# Alight_main_board_v3.net
KiCad netlist of a schematic drawn in EAGLE
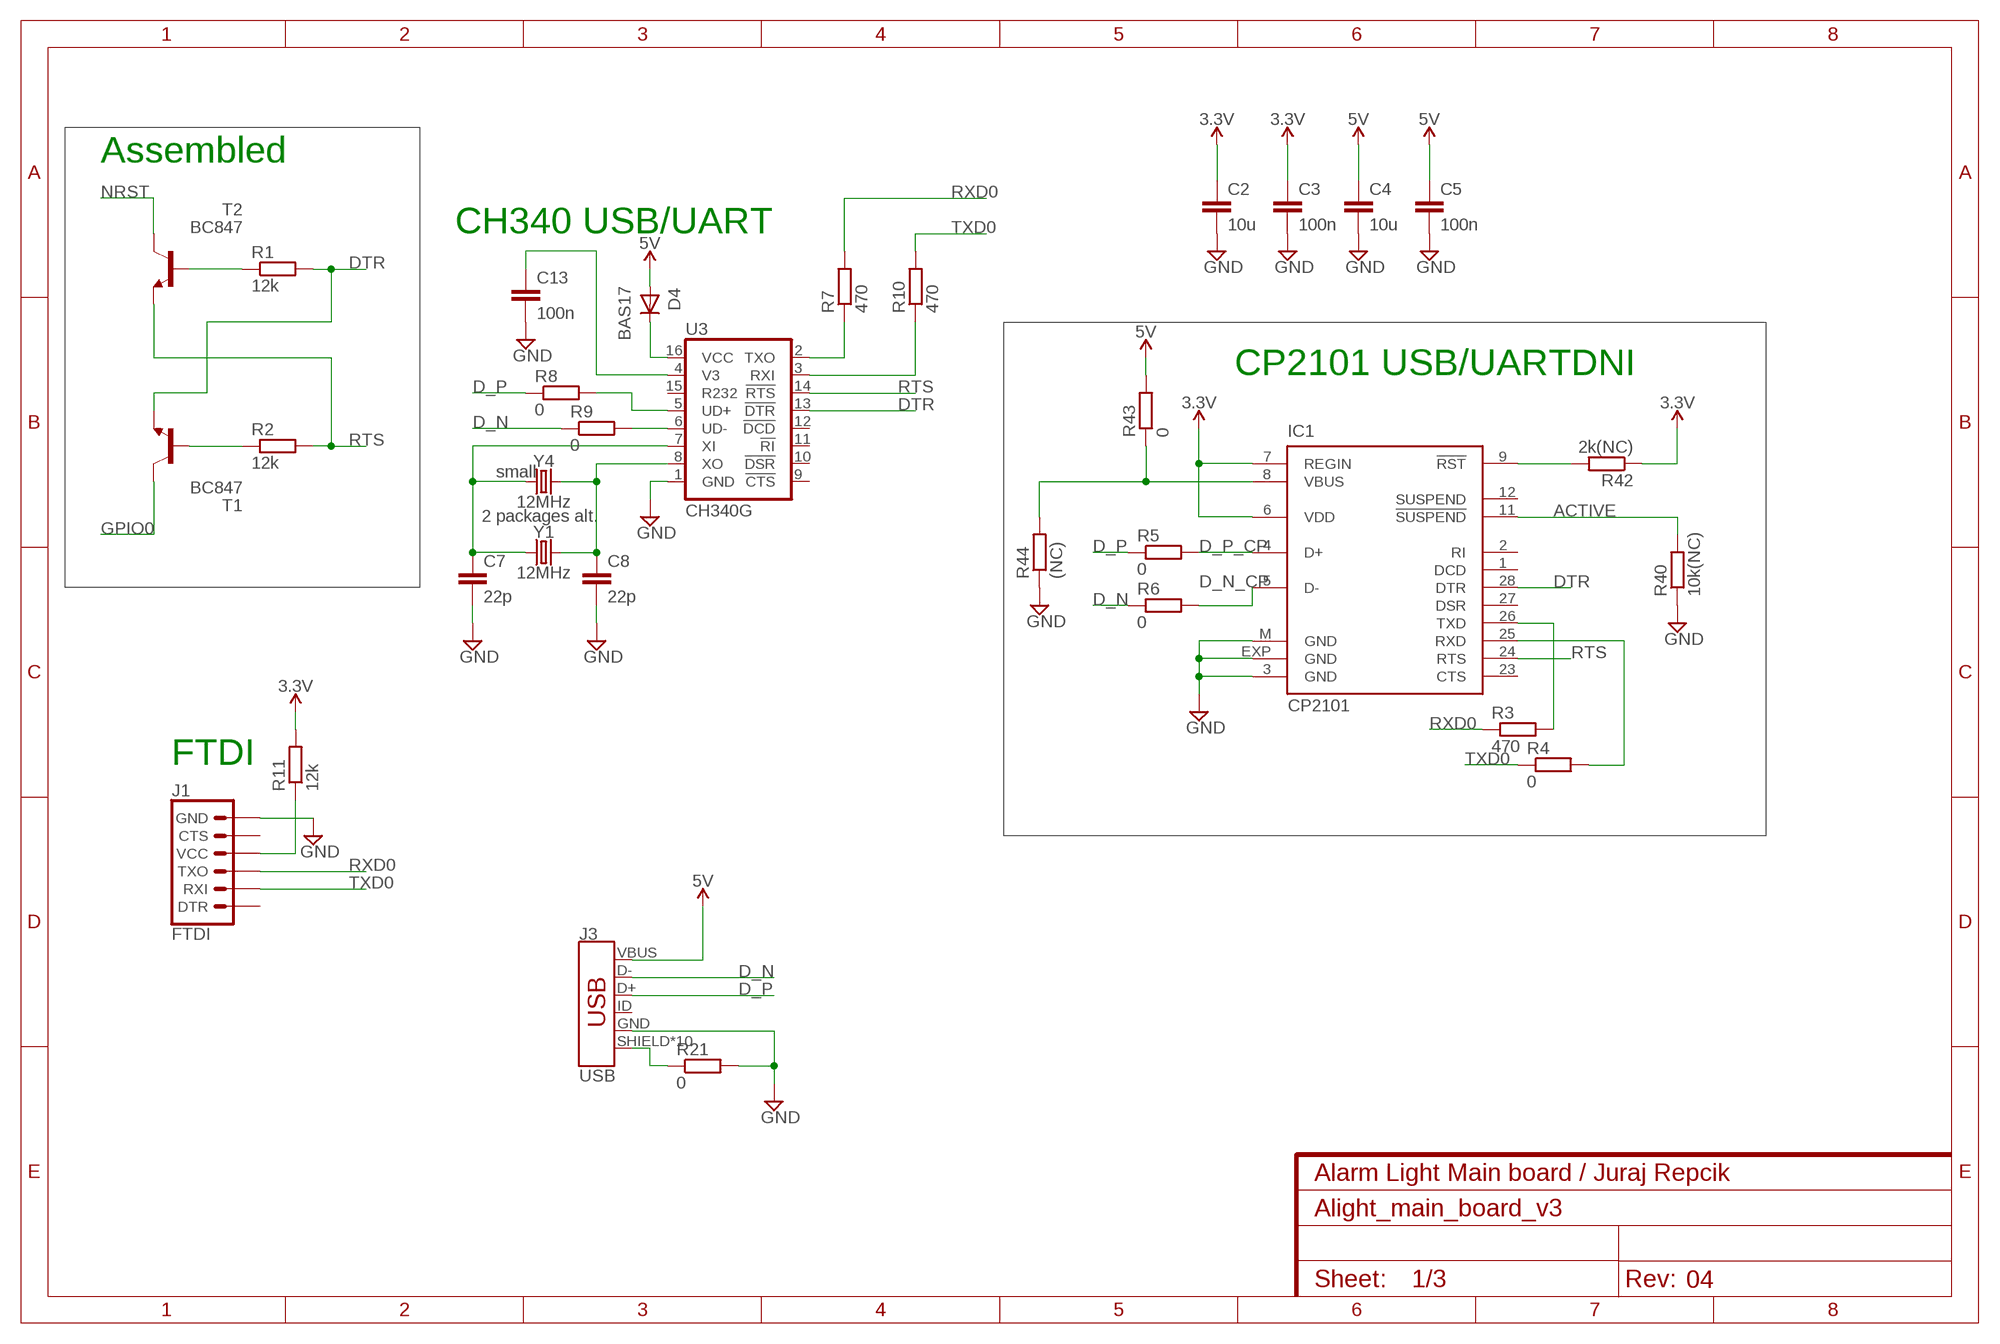
[diagram p0: schematic, sheet 1]
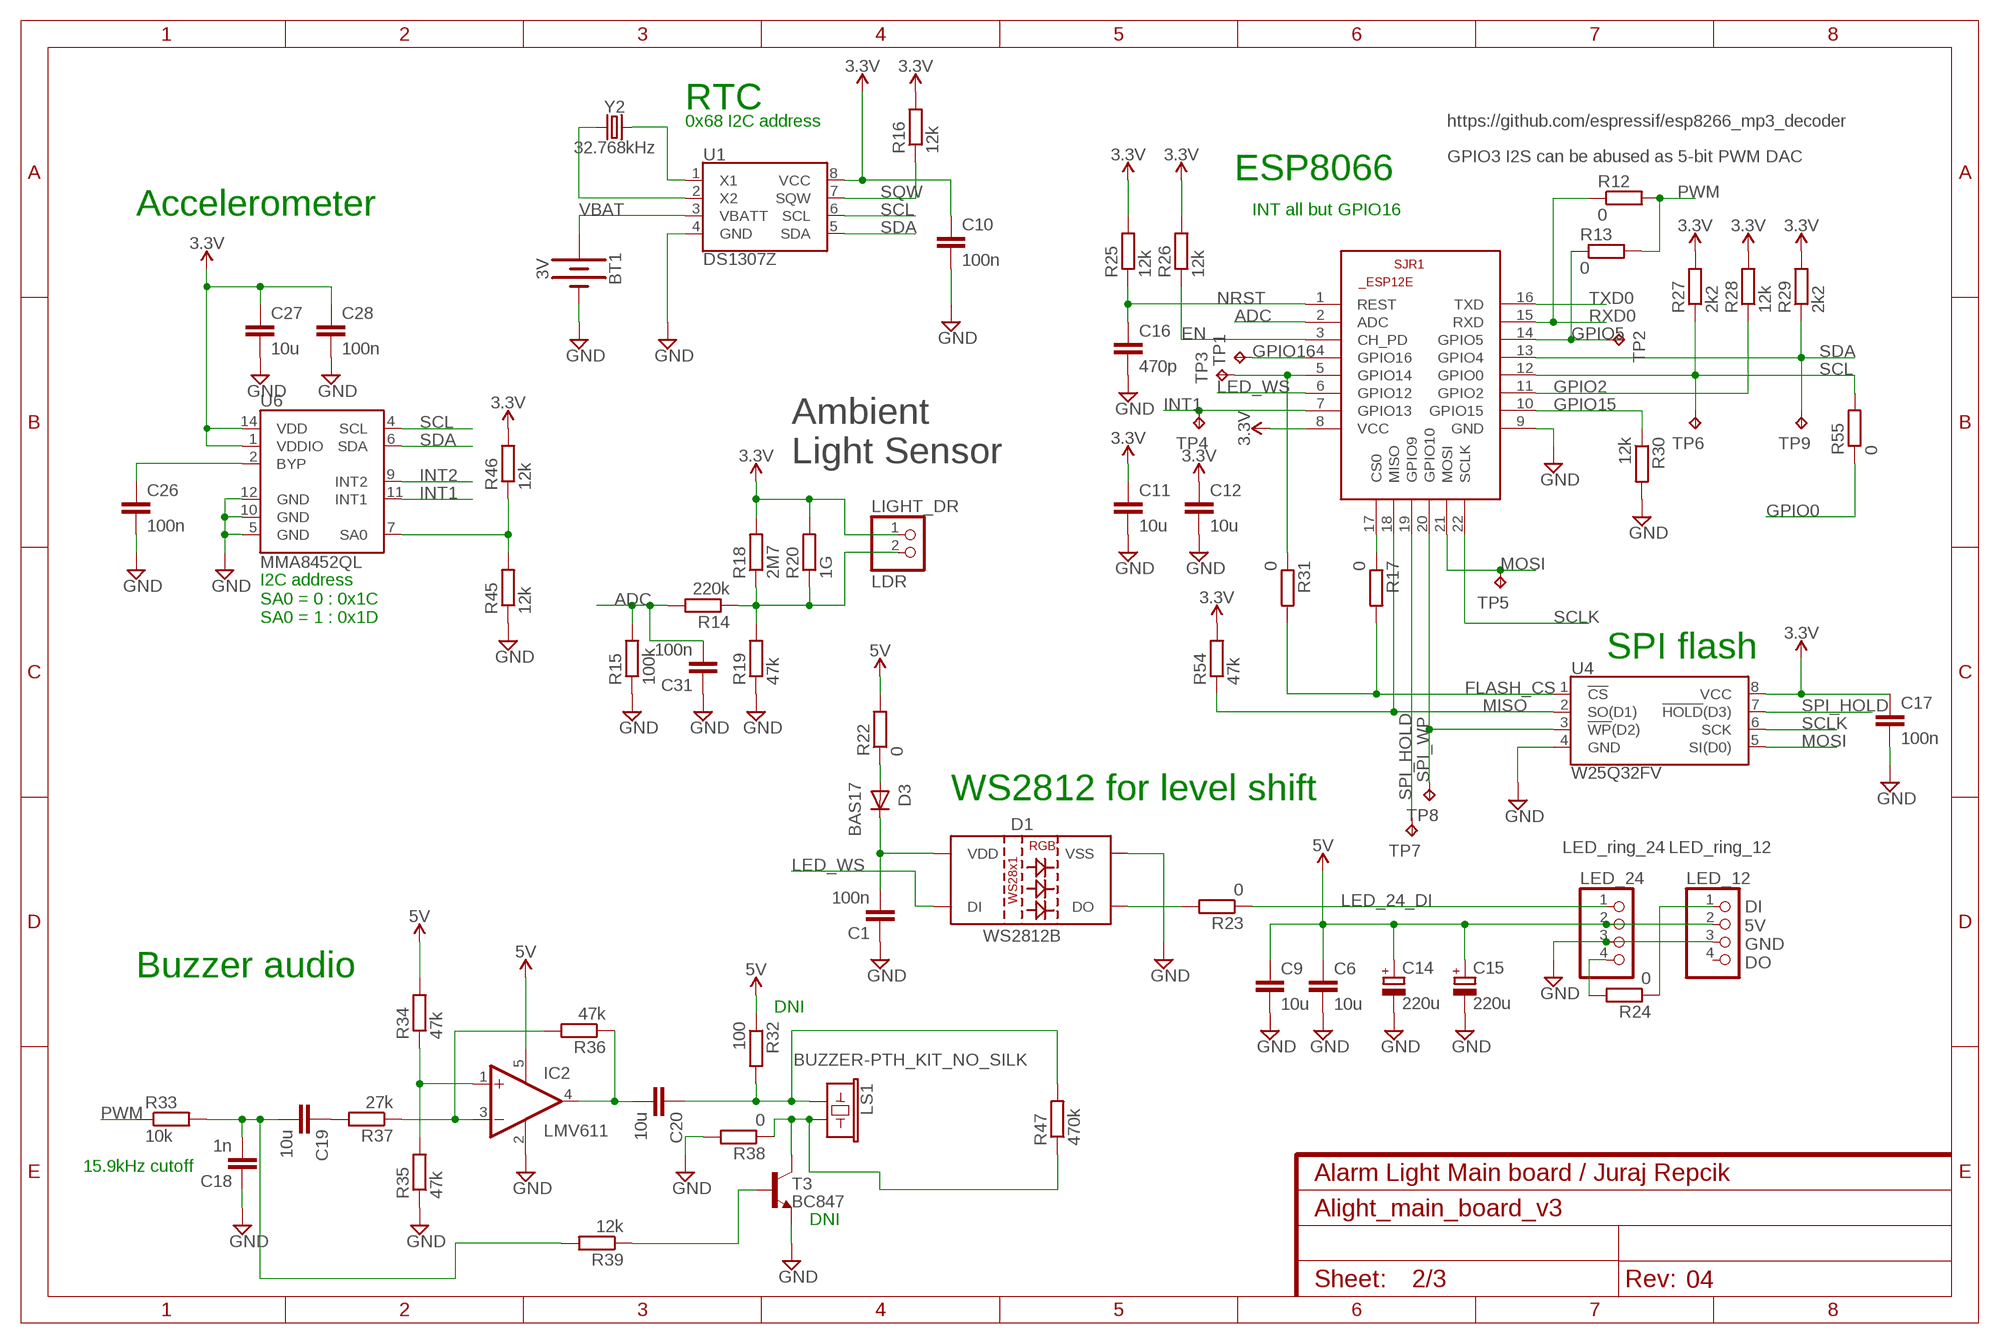
[diagram p1: schematic, sheet 2]
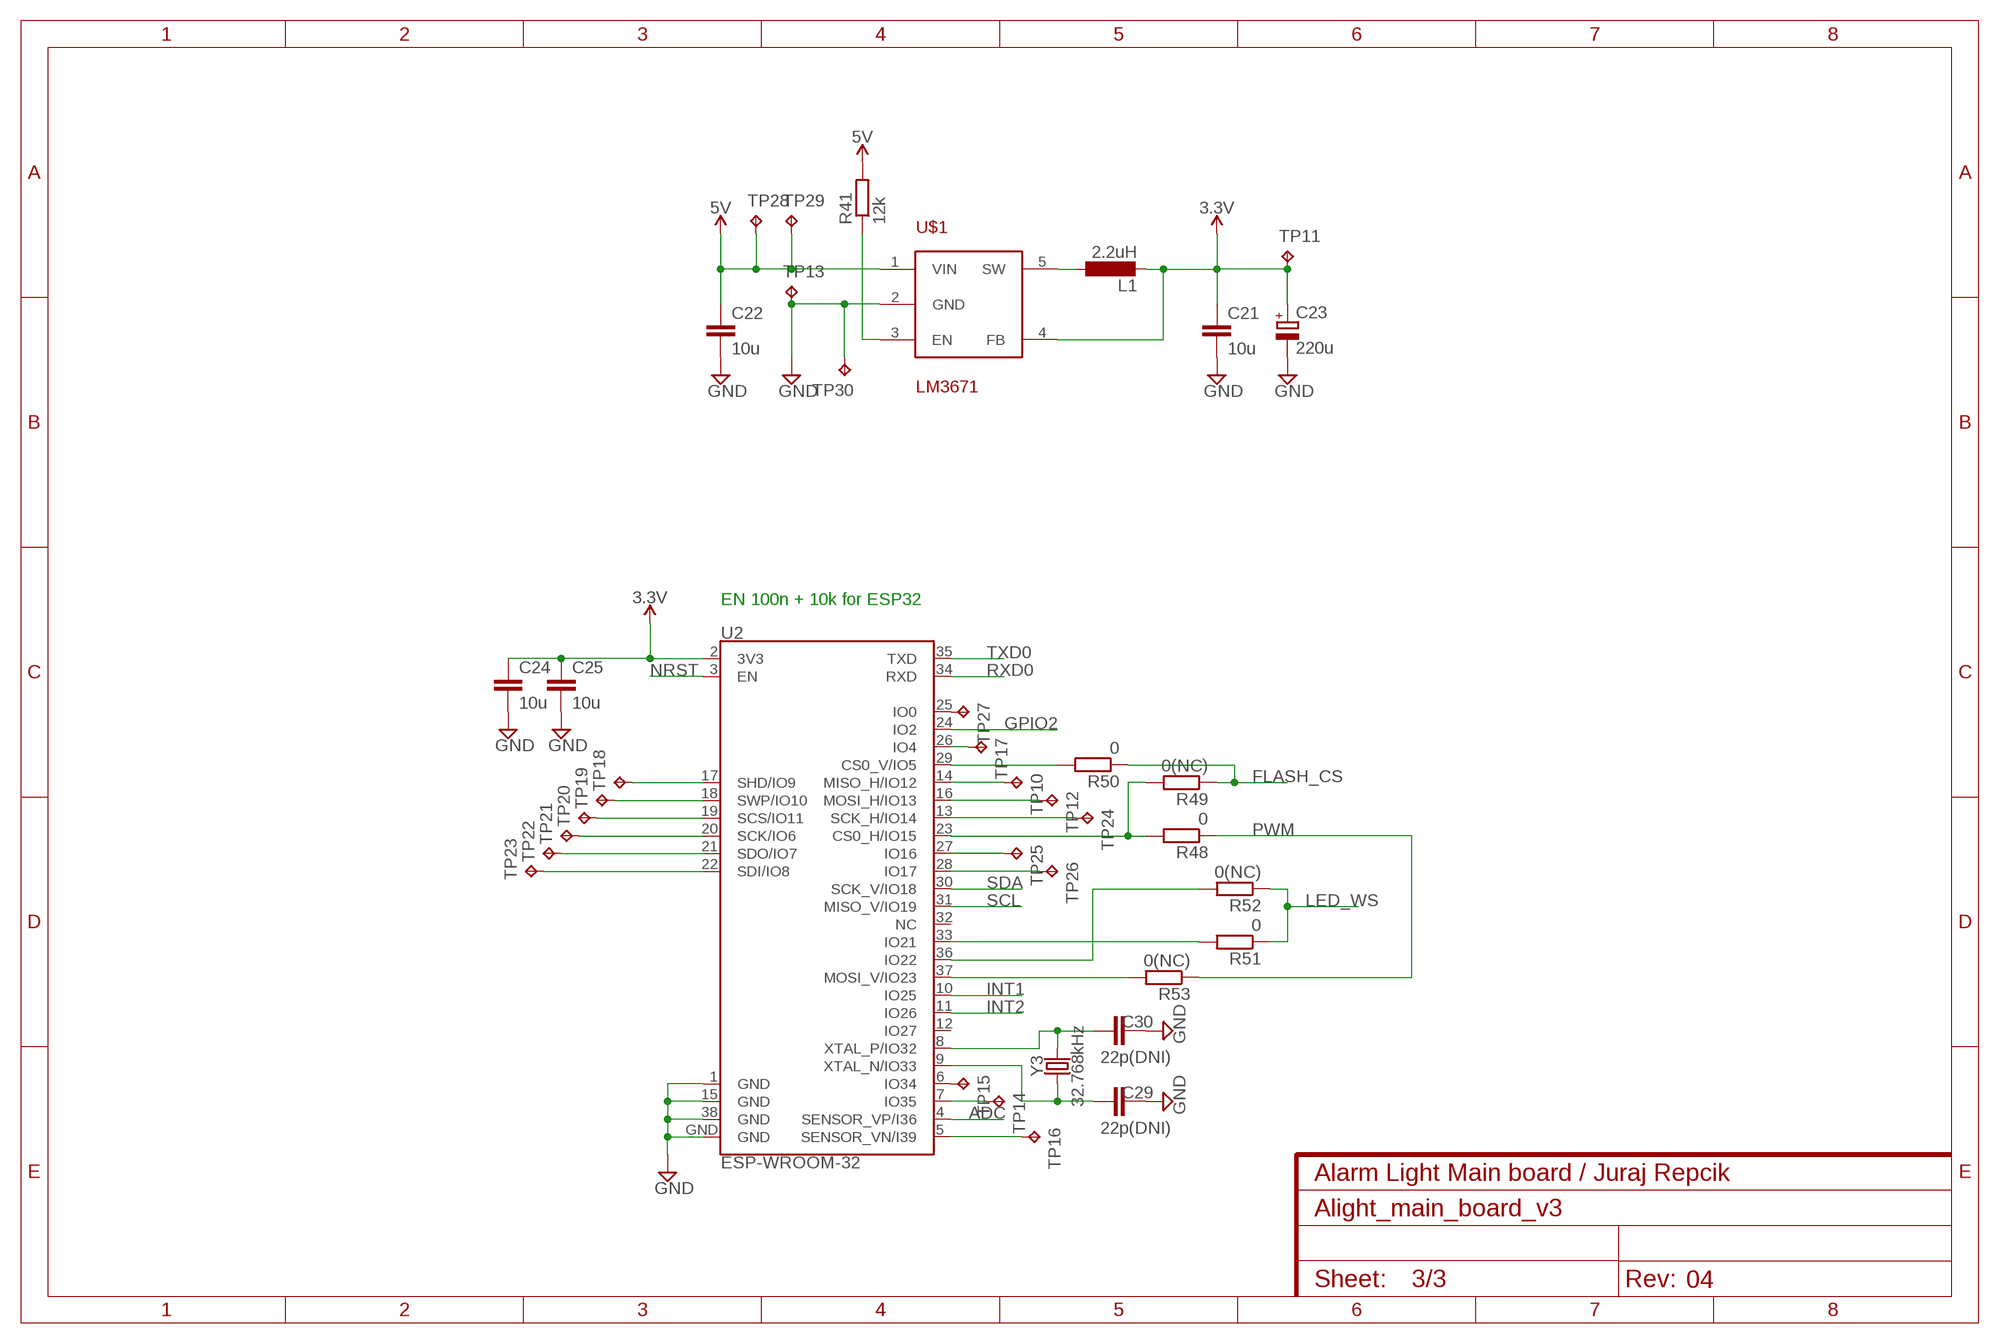
[diagram p2: schematic, sheet 3]

(export (version "E")
  (design (tool "Eeschema 10.0.6"))
  (components
    (comp (ref "C2")
      (value "10u")
      (footprint "eagle-import:C0603K")
      (libsource (lib "eagle-import") (part "C-EUC0603K"))
    )
    (comp (ref "C3")
      (value "100n")
      (footprint "eagle-import:C0603K")
      (libsource (lib "eagle-import") (part "C-EUC0603K"))
    )
    (comp (ref "C4")
      (value "10u")
      (footprint "eagle-import:C0603K")
      (libsource (lib "eagle-import") (part "C-EUC0603K"))
    )
    (comp (ref "C5")
      (value "100n")
      (footprint "eagle-import:C0603K")
      (libsource (lib "eagle-import") (part "C-EUC0603K"))
    )
    (comp (ref "C7")
      (value "22p")
      (footprint "eagle-import:C0402")
      (libsource (lib "eagle-import") (part "C-EUC0402"))
    )
    (comp (ref "C8")
      (value "22p")
      (footprint "eagle-import:C0402")
      (libsource (lib "eagle-import") (part "C-EUC0402"))
    )
    (comp (ref "C13")
      (value "100n")
      (footprint "eagle-import:C0603K")
      (libsource (lib "eagle-import") (part "C-EUC0603K"))
    )
    (comp (ref "D4")
      (value "BAS17")
      (footprint "eagle-import:SOT23")
      (libsource (lib "eagle-import") (part "BAS17"))
    )
    (comp (ref "IC1")
      (value "CP2101")
      (footprint "eagle-import:MLP28")
      (libsource (lib "eagle-import") (part "CP210X_USB_UART"))
    )
    (comp (ref "J1")
      (value "FTDI")
      (footprint "eagle-import:1X06_LONGPADS")
      (libsource (lib "eagle-import") (part "6_PIN_SERIAL_TARGETLONGPADS"))
    )
    (comp (ref "J3")
      (value "USB")
      (footprint "eagle-import:USB-MICROB-PTH-MILL")
      (libsource (lib "eagle-import") (part "USB_MICRO-B_HALF_PTH_MILL"))
    )
    (comp (ref "R1")
      (value "12k")
      (footprint "eagle-import:R0603")
      (libsource (lib "eagle-import") (part "R-EU_R0603"))
    )
    (comp (ref "R2")
      (value "12k")
      (footprint "eagle-import:R0603")
      (libsource (lib "eagle-import") (part "R-EU_R0603"))
    )
    (comp (ref "R3")
      (value "470")
      (footprint "eagle-import:R0603")
      (libsource (lib "eagle-import") (part "R-EU_R0603"))
    )
    (comp (ref "R4")
      (value "0")
      (footprint "eagle-import:R0603")
      (libsource (lib "eagle-import") (part "R-EU_R0603"))
    )
    (comp (ref "R5")
      (value "0")
      (footprint "eagle-import:R0603")
      (libsource (lib "eagle-import") (part "R-EU_R0603"))
    )
    (comp (ref "R6")
      (value "0")
      (footprint "eagle-import:R0603")
      (libsource (lib "eagle-import") (part "R-EU_R0603"))
    )
    (comp (ref "R7")
      (value "470")
      (footprint "eagle-import:R0603")
      (libsource (lib "eagle-import") (part "R-EU_R0603"))
    )
    (comp (ref "R8")
      (value "0")
      (footprint "eagle-import:R0603")
      (libsource (lib "eagle-import") (part "R-EU_R0603"))
    )
    (comp (ref "R9")
      (value "0")
      (footprint "eagle-import:R0603")
      (libsource (lib "eagle-import") (part "R-EU_R0603"))
    )
    (comp (ref "R10")
      (value "470")
      (footprint "eagle-import:R0603")
      (libsource (lib "eagle-import") (part "R-EU_R0603"))
    )
    (comp (ref "R11")
      (value "12k")
      (footprint "eagle-import:R0603")
      (libsource (lib "eagle-import") (part "R-EU_R0603"))
    )
    (comp (ref "R21")
      (value "0")
      (footprint "eagle-import:R0603")
      (libsource (lib "eagle-import") (part "R-EU_R0603"))
    )
    (comp (ref "R40")
      (value "10k(NC)")
      (footprint "eagle-import:R0603")
      (libsource (lib "eagle-import") (part "R-EU_R0603"))
    )
    (comp (ref "R42")
      (value "2k(NC)")
      (footprint "eagle-import:R0603")
      (libsource (lib "eagle-import") (part "R-EU_R0603"))
    )
    (comp (ref "R43")
      (value "0")
      (footprint "eagle-import:R0603")
      (libsource (lib "eagle-import") (part "R-EU_R0603"))
    )
    (comp (ref "R44")
      (value "(NC)")
      (footprint "eagle-import:R0603")
      (libsource (lib "eagle-import") (part "R-EU_R0603"))
    )
    (comp (ref "T1")
      (value "BC847")
      (footprint "eagle-import:SOT23")
      (libsource (lib "eagle-import") (part "transistor-neu-to92_BC847"))
    )
    (comp (ref "T2")
      (value "BC847")
      (footprint "eagle-import:SOT23")
      (libsource (lib "eagle-import") (part "transistor-neu-to92_BC847"))
    )
    (comp (ref "U3")
      (value "CH340G")
      (footprint "eagle-import:SO016")
      (libsource (lib "eagle-import") (part "CH340GSMD"))
    )
    (comp (ref "Y1")
      (value "12MHz")
      (footprint "eagle-import:HC49UP")
      (libsource (lib "eagle-import") (part "CRYSTALSMD-HC49UP"))
    )
    (comp (ref "Y4")
      (value "12MHz")
      (footprint "eagle-import:CRYSTAL-SMD-3.2X1.5MM")
      (libsource (lib "eagle-import") (part "CRYSTAL-32.768KHZSMD-3.2X1.5"))
    )
    (comp (ref "C21")
      (value "10u")
      (footprint "eagle-import:C0603K")
      (libsource (lib "eagle-import") (part "C-EUC0603K"))
    )
    (comp (ref "C22")
      (value "10u")
      (footprint "eagle-import:C0603K")
      (libsource (lib "eagle-import") (part "C-EUC0603K"))
    )
    (comp (ref "C23")
      (value "220u")
      (footprint "eagle-import:153CLV-0605")
      (libsource (lib "eagle-import") (part "CPOL-EU153CLV-0605"))
    )
    (comp (ref "C24")
      (value "10u")
      (footprint "eagle-import:C0603K")
      (libsource (lib "eagle-import") (part "C-EUC0603K"))
    )
    (comp (ref "C25")
      (value "10u")
      (footprint "eagle-import:C0603K")
      (libsource (lib "eagle-import") (part "C-EUC0603K"))
    )
    (comp (ref "C29")
      (value "22p(DNI)")
      (footprint "eagle-import:C0402")
      (libsource (lib "eagle-import") (part "C-EUC0402"))
    )
    (comp (ref "C30")
      (value "22p(DNI)")
      (footprint "eagle-import:C0402")
      (libsource (lib "eagle-import") (part "C-EUC0402"))
    )
    (comp (ref "L1")
      (value "2.2uH")
      (footprint "eagle-import:L3225M")
      (libsource (lib "eagle-import") (part "L-EUL3225M"))
    )
    (comp (ref "R41")
      (value "12k")
      (footprint "eagle-import:R0603")
      (libsource (lib "eagle-import") (part "R-EU_R0603"))
    )
    (comp (ref "R48")
      (value "0")
      (footprint "eagle-import:R0603")
      (libsource (lib "eagle-import") (part "R-EU_R0603"))
    )
    (comp (ref "R49")
      (value "0(NC)")
      (footprint "eagle-import:R0603")
      (libsource (lib "eagle-import") (part "R-EU_R0603"))
    )
    (comp (ref "R50")
      (value "0")
      (footprint "eagle-import:R0603")
      (libsource (lib "eagle-import") (part "R-EU_R0603"))
    )
    (comp (ref "R51")
      (value "0")
      (footprint "eagle-import:R0603")
      (libsource (lib "eagle-import") (part "R-EU_R0603"))
    )
    (comp (ref "R52")
      (value "0(NC)")
      (footprint "eagle-import:R0603")
      (libsource (lib "eagle-import") (part "R-EU_R0603"))
    )
    (comp (ref "R53")
      (value "0(NC)")
      (footprint "eagle-import:R0603")
      (libsource (lib "eagle-import") (part "R-EU_R0603"))
    )
    (comp (ref "TP10")
      (value "TPTP10R")
      (footprint "eagle-import:TP10R")
      (libsource (lib "eagle-import") (part "TPTP10R"))
    )
    (comp (ref "TP11")
      (value "TPTP10R")
      (footprint "eagle-import:TP10R")
      (libsource (lib "eagle-import") (part "TPTP10R"))
    )
    (comp (ref "TP12")
      (value "TPTP10R")
      (footprint "eagle-import:TP10R")
      (libsource (lib "eagle-import") (part "TPTP10R"))
    )
    (comp (ref "TP13")
      (value "TPTP10R")
      (footprint "eagle-import:TP10R")
      (libsource (lib "eagle-import") (part "TPTP10R"))
    )
    (comp (ref "TP14")
      (value "TPTP10R")
      (footprint "eagle-import:TP10R")
      (libsource (lib "eagle-import") (part "TPTP10R"))
    )
    (comp (ref "TP15")
      (value "TPTP10R")
      (footprint "eagle-import:TP10R")
      (libsource (lib "eagle-import") (part "TPTP10R"))
    )
    (comp (ref "TP16")
      (value "TPTP10R")
      (footprint "eagle-import:TP10R")
      (libsource (lib "eagle-import") (part "TPTP10R"))
    )
    (comp (ref "TP17")
      (value "TPTP10R")
      (footprint "eagle-import:TP10R")
      (libsource (lib "eagle-import") (part "TPTP10R"))
    )
    (comp (ref "TP18")
      (value "TPTP10R")
      (footprint "eagle-import:TP10R")
      (libsource (lib "eagle-import") (part "TPTP10R"))
    )
    (comp (ref "TP19")
      (value "TPTP10R")
      (footprint "eagle-import:TP10R")
      (libsource (lib "eagle-import") (part "TPTP10R"))
    )
    (comp (ref "TP20")
      (value "TPTP10R")
      (footprint "eagle-import:TP10R")
      (libsource (lib "eagle-import") (part "TPTP10R"))
    )
    (comp (ref "TP21")
      (value "TPTP10R")
      (footprint "eagle-import:TP10R")
      (libsource (lib "eagle-import") (part "TPTP10R"))
    )
    (comp (ref "TP22")
      (value "TPTP10R")
      (footprint "eagle-import:TP10R")
      (libsource (lib "eagle-import") (part "TPTP10R"))
    )
    (comp (ref "TP23")
      (value "TPTP10R")
      (footprint "eagle-import:TP10R")
      (libsource (lib "eagle-import") (part "TPTP10R"))
    )
    (comp (ref "TP24")
      (value "TPTP10R")
      (footprint "eagle-import:TP10R")
      (libsource (lib "eagle-import") (part "TPTP10R"))
    )
    (comp (ref "TP25")
      (value "TPTP10R")
      (footprint "eagle-import:TP10R")
      (libsource (lib "eagle-import") (part "TPTP10R"))
    )
    (comp (ref "TP26")
      (value "TPTP10R")
      (footprint "eagle-import:TP10R")
      (libsource (lib "eagle-import") (part "TPTP10R"))
    )
    (comp (ref "TP27")
      (value "TPTP10R")
      (footprint "eagle-import:TP10R")
      (libsource (lib "eagle-import") (part "TPTP10R"))
    )
    (comp (ref "TP28")
      (value "TPTP10R")
      (footprint "eagle-import:TP10R")
      (libsource (lib "eagle-import") (part "TPTP10R"))
    )
    (comp (ref "TP29")
      (value "TPTP10R")
      (footprint "eagle-import:TP10R")
      (libsource (lib "eagle-import") (part "TPTP10R"))
    )
    (comp (ref "TP30")
      (value "TPTP10R")
      (footprint "eagle-import:TP10R")
      (libsource (lib "eagle-import") (part "TPTP10R"))
    )
    (comp (ref "U$1")
      (value "LM3671")
      (footprint "eagle-import:SOT23-5")
      (libsource (lib "eagle-import") (part "LM3671"))
    )
    (comp (ref "U2")
      (value "ESP-WROOM-32")
      (footprint "eagle-import:ESP-WROOM-32")
      (libsource (lib "eagle-import") (part "ESP-WROOM-32"))
    )
    (comp (ref "Y3")
      (value "32.768kHz")
      (footprint "eagle-import:CRYSTAL-SMD-3.2X1.5MM")
      (libsource (lib "eagle-import") (part "CRYSTAL-32.768KHZSMD-3.2X1.5"))
    )
    (comp (ref "BT1")
      (value "3V")
      (footprint "eagle-import:BATTCOM_20MM_PTH_KIT")
      (libsource (lib "eagle-import") (part "BATTERY-20MM_PTH_KIT"))
    )
    (comp (ref "C1")
      (value "100n")
      (footprint "eagle-import:C0603K")
      (libsource (lib "eagle-import") (part "C-EUC0603K"))
    )
    (comp (ref "C6")
      (value "10u")
      (footprint "eagle-import:C0603K")
      (libsource (lib "eagle-import") (part "C-EUC0603K"))
    )
    (comp (ref "C9")
      (value "10u")
      (footprint "eagle-import:C0603K")
      (libsource (lib "eagle-import") (part "C-EUC0603K"))
    )
    (comp (ref "C10")
      (value "100n")
      (footprint "eagle-import:C0603K")
      (libsource (lib "eagle-import") (part "C-EUC0603K"))
    )
    (comp (ref "C11")
      (value "10u")
      (footprint "eagle-import:C0603K")
      (libsource (lib "eagle-import") (part "C-EUC0603K"))
    )
    (comp (ref "C12")
      (value "10u")
      (footprint "eagle-import:C0603K")
      (libsource (lib "eagle-import") (part "C-EUC0603K"))
    )
    (comp (ref "C14")
      (value "220u")
      (footprint "eagle-import:153CLV-0605")
      (libsource (lib "eagle-import") (part "CPOL-EU153CLV-0605"))
    )
    (comp (ref "C15")
      (value "220u")
      (footprint "eagle-import:153CLV-0605")
      (libsource (lib "eagle-import") (part "CPOL-EU153CLV-0605"))
    )
    (comp (ref "C16")
      (value "470p")
      (footprint "eagle-import:C0603K")
      (libsource (lib "eagle-import") (part "C-EUC0603K"))
    )
    (comp (ref "C17")
      (value "100n")
      (footprint "eagle-import:C0603K")
      (libsource (lib "eagle-import") (part "C-EUC0603K"))
    )
    (comp (ref "C18")
      (value "1n")
      (footprint "eagle-import:C0603K")
      (libsource (lib "eagle-import") (part "C-EUC0603K"))
    )
    (comp (ref "C19")
      (value "10u")
      (footprint "eagle-import:C0603K")
      (libsource (lib "eagle-import") (part "C-EUC0603K"))
    )
    (comp (ref "C20")
      (value "10u")
      (footprint "eagle-import:C0603K")
      (libsource (lib "eagle-import") (part "C-EUC0603K"))
    )
    (comp (ref "C26")
      (value "100n")
      (footprint "eagle-import:C0603K")
      (libsource (lib "eagle-import") (part "C-EUC0603K"))
    )
    (comp (ref "C27")
      (value "10u")
      (footprint "eagle-import:C0603K")
      (libsource (lib "eagle-import") (part "C-EUC0603K"))
    )
    (comp (ref "C28")
      (value "100n")
      (footprint "eagle-import:C0603K")
      (libsource (lib "eagle-import") (part "C-EUC0603K"))
    )
    (comp (ref "C31")
      (value "100n")
      (footprint "eagle-import:C0603K")
      (libsource (lib "eagle-import") (part "C-EUC0603K"))
    )
    (comp (ref "D1")
      (value "WS2812B")
      (footprint "eagle-import:WS2812B")
      (libsource (lib "eagle-import") (part "WS2812B"))
    )
    (comp (ref "D3")
      (value "BAS17")
      (footprint "eagle-import:SOT23")
      (libsource (lib "eagle-import") (part "BAS17"))
    )
    (comp (ref "IC2")
      (value "LMV611")
      (footprint "eagle-import:SC70-5L")
      (libsource (lib "eagle-import") (part "OPA333DCK"))
    )
    (comp (ref "LED_12")
      (value "LED_ring_12")
      (footprint "eagle-import:1X04")
      (libsource (lib "eagle-import") (part "PINHD-1X4"))
    )
    (comp (ref "LED_24")
      (value "LED_ring_24")
      (footprint "eagle-import:1X04")
      (libsource (lib "eagle-import") (part "PINHD-1X4"))
    )
    (comp (ref "LIGHT_DR")
      (value "LDR")
      (footprint "eagle-import:1X02")
      (libsource (lib "eagle-import") (part "PINHD-1X2"))
    )
    (comp (ref "LS1")
      (value "BUZZER-PTH_KIT_NO_SILK")
      (footprint "eagle-import:BUZZER-12MM-NS-KIT")
      (libsource (lib "eagle-import") (part "BUZZER-PTH_KIT_NO_SILK"))
    )
    (comp (ref "R12")
      (value "0")
      (footprint "eagle-import:R0603")
      (libsource (lib "eagle-import") (part "R-EU_R0603"))
    )
    (comp (ref "R13")
      (value "0")
      (footprint "eagle-import:R0603")
      (libsource (lib "eagle-import") (part "R-EU_R0603"))
    )
    (comp (ref "R14")
      (value "220k")
      (footprint "eagle-import:R0603")
      (libsource (lib "eagle-import") (part "R-EU_R0603"))
    )
    (comp (ref "R15")
      (value "100k")
      (footprint "eagle-import:R0603")
      (libsource (lib "eagle-import") (part "R-EU_R0603"))
    )
    (comp (ref "R16")
      (value "12k")
      (footprint "eagle-import:R0603")
      (libsource (lib "eagle-import") (part "R-EU_R0603"))
    )
    (comp (ref "R17")
      (value "0")
      (footprint "eagle-import:R0603")
      (libsource (lib "eagle-import") (part "R-EU_R0603"))
    )
    (comp (ref "R18")
      (value "2M7")
      (footprint "eagle-import:R0603")
      (libsource (lib "eagle-import") (part "R-EU_R0603"))
    )
    (comp (ref "R19")
      (value "47k")
      (footprint "eagle-import:R0603")
      (libsource (lib "eagle-import") (part "R-EU_R0603"))
    )
    (comp (ref "R20")
      (value "1G")
      (footprint "eagle-import:R0603")
      (libsource (lib "eagle-import") (part "R-EU_R0603"))
    )
    (comp (ref "R22")
      (value "0")
      (footprint "eagle-import:R0603")
      (libsource (lib "eagle-import") (part "R-EU_R0603"))
    )
    (comp (ref "R23")
      (value "0")
      (footprint "eagle-import:R0603")
      (libsource (lib "eagle-import") (part "R-EU_R0603"))
    )
    (comp (ref "R24")
      (value "0")
      (footprint "eagle-import:R0603")
      (libsource (lib "eagle-import") (part "R-EU_R0603"))
    )
    (comp (ref "R25")
      (value "12k")
      (footprint "eagle-import:R0603")
      (libsource (lib "eagle-import") (part "R-EU_R0603"))
    )
    (comp (ref "R26")
      (value "12k")
      (footprint "eagle-import:R0603")
      (libsource (lib "eagle-import") (part "R-EU_R0603"))
    )
    (comp (ref "R27")
      (value "2k2")
      (footprint "eagle-import:R0603")
      (libsource (lib "eagle-import") (part "R-EU_R0603"))
    )
    (comp (ref "R28")
      (value "12k")
      (footprint "eagle-import:R0603")
      (libsource (lib "eagle-import") (part "R-EU_R0603"))
    )
    (comp (ref "R29")
      (value "2k2")
      (footprint "eagle-import:R0603")
      (libsource (lib "eagle-import") (part "R-EU_R0603"))
    )
    (comp (ref "R30")
      (value "12k")
      (footprint "eagle-import:R0603")
      (libsource (lib "eagle-import") (part "R-EU_R0603"))
    )
    (comp (ref "R31")
      (value "0")
      (footprint "eagle-import:R0603")
      (libsource (lib "eagle-import") (part "R-EU_R0603"))
    )
    (comp (ref "R32")
      (value "100")
      (footprint "eagle-import:R0603")
      (libsource (lib "eagle-import") (part "R-EU_R0603"))
    )
    (comp (ref "R33")
      (value "10k")
      (footprint "eagle-import:R0603")
      (libsource (lib "eagle-import") (part "R-EU_R0603"))
    )
    (comp (ref "R34")
      (value "47k")
      (footprint "eagle-import:R0603")
      (libsource (lib "eagle-import") (part "R-EU_R0603"))
    )
    (comp (ref "R35")
      (value "47k")
      (footprint "eagle-import:R0603")
      (libsource (lib "eagle-import") (part "R-EU_R0603"))
    )
    (comp (ref "R36")
      (value "47k")
      (footprint "eagle-import:R0603")
      (libsource (lib "eagle-import") (part "R-EU_R0603"))
    )
    (comp (ref "R37")
      (value "27k")
      (footprint "eagle-import:R0603")
      (libsource (lib "eagle-import") (part "R-EU_R0603"))
    )
    (comp (ref "R38")
      (value "0")
      (footprint "eagle-import:R0603")
      (libsource (lib "eagle-import") (part "R-EU_R0603"))
    )
    (comp (ref "R39")
      (value "12k")
      (footprint "eagle-import:R0603")
      (libsource (lib "eagle-import") (part "R-EU_R0603"))
    )
    (comp (ref "R45")
      (value "12k")
      (footprint "eagle-import:R0603")
      (libsource (lib "eagle-import") (part "R-EU_R0603"))
    )
    (comp (ref "R46")
      (value "12k")
      (footprint "eagle-import:R0603")
      (libsource (lib "eagle-import") (part "R-EU_R0603"))
    )
    (comp (ref "R47")
      (value "470k")
      (footprint "eagle-import:R0603")
      (libsource (lib "eagle-import") (part "R-EU_R0603"))
    )
    (comp (ref "R54")
      (value "47k")
      (footprint "eagle-import:R0603")
      (libsource (lib "eagle-import") (part "R-EU_R0603"))
    )
    (comp (ref "R55")
      (value "0")
      (footprint "eagle-import:R0603")
      (libsource (lib "eagle-import") (part "R-EU_R0603"))
    )
    (comp (ref "SJR1")
      (value "ESP12E/F")
      (footprint "eagle-import:ESP8266-ESP12E")
      (libsource (lib "eagle-import") (part "ESP8266-12EESP12E"))
    )
    (comp (ref "T3")
      (value "BC847")
      (footprint "eagle-import:SOT23")
      (libsource (lib "eagle-import") (part "BC847"))
    )
    (comp (ref "TP1")
      (value "TPTP10R")
      (footprint "eagle-import:TP10R")
      (libsource (lib "eagle-import") (part "TPTP10R"))
    )
    (comp (ref "TP2")
      (value "TPTP10R")
      (footprint "eagle-import:TP10R")
      (libsource (lib "eagle-import") (part "TPTP10R"))
    )
    (comp (ref "TP3")
      (value "TPTP10R")
      (footprint "eagle-import:TP10R")
      (libsource (lib "eagle-import") (part "TPTP10R"))
    )
    (comp (ref "TP4")
      (value "TPTP10R")
      (footprint "eagle-import:TP10R")
      (libsource (lib "eagle-import") (part "TPTP10R"))
    )
    (comp (ref "TP5")
      (value "TPTP10R")
      (footprint "eagle-import:TP10R")
      (libsource (lib "eagle-import") (part "TPTP10R"))
    )
    (comp (ref "TP6")
      (value "TPTP10R")
      (footprint "eagle-import:TP10R")
      (libsource (lib "eagle-import") (part "TPTP10R"))
    )
    (comp (ref "TP7")
      (value "TPTP10R")
      (footprint "eagle-import:TP10R")
      (libsource (lib "eagle-import") (part "TPTP10R"))
    )
    (comp (ref "TP8")
      (value "TPTP10R")
      (footprint "eagle-import:TP10R")
      (libsource (lib "eagle-import") (part "TPTP10R"))
    )
    (comp (ref "TP9")
      (value "TPTP10R")
      (footprint "eagle-import:TP10R")
      (libsource (lib "eagle-import") (part "TPTP10R"))
    )
    (comp (ref "U1")
      (value "DS1307Z")
      (footprint "eagle-import:SO08-0.15")
      (libsource (lib "eagle-import") (part "DS1307Z"))
    )
    (comp (ref "U4")
      (value "W25Q32FV")
      (footprint "eagle-import:SOIC-8")
      (libsource (lib "eagle-import") (part "W25Q32FVSS"))
    )
    (comp (ref "U6")
      (value "MMA8452QL")
      (footprint "eagle-import:QFN-16_0.5MM-EXTRA")
      (fields (field (name "MF") "NXP Semiconductors") (field (name "MP") "MMA8452Q"))
      (libsource (lib "eagle-import") (part "MMA8452QL"))
    )
    (comp (ref "Y2")
      (value "32.768kHz")
      (footprint "eagle-import:CRYSTAL-SMD-3.2X1.5MM")
      (libsource (lib "eagle-import") (part "CRYSTAL-32.768KHZSMD-3.2X1.5"))
    )
  )
  (nets
    (net (code "1") (name "3.3V") (class "Default")
      (node (ref "C10") (pin "1") (pinfunction "1_1") (pintype "passive"))
      (node (ref "C11") (pin "1") (pinfunction "1_1") (pintype "passive"))
      (node (ref "C12") (pin "1") (pinfunction "1_1") (pintype "passive"))
      (node (ref "C17") (pin "1") (pinfunction "1_1") (pintype "passive"))
      (node (ref "C2") (pin "1") (pinfunction "1_1") (pintype "passive"))
      (node (ref "C21") (pin "1") (pinfunction "1_1") (pintype "passive"))
      (node (ref "C23") (pin "+") (pinfunction "+_+") (pintype "passive"))
      (node (ref "C24") (pin "1") (pinfunction "1_1") (pintype "passive"))
      (node (ref "C25") (pin "1") (pinfunction "1_1") (pintype "passive"))
      (node (ref "C27") (pin "1") (pinfunction "1_1") (pintype "passive"))
      (node (ref "C28") (pin "1") (pinfunction "1_1") (pintype "passive"))
      (node (ref "C3") (pin "1") (pinfunction "1_1") (pintype "passive"))
      (node (ref "IC1") (pin "6") (pinfunction "VDD_6") (pintype "power_in"))
      (node (ref "IC1") (pin "7") (pinfunction "REGIN_7") (pintype "passive"))
      (node (ref "L1") (pin "2") (pinfunction "2_2") (pintype "passive"))
      (node (ref "LIGHT_DR") (pin "1") (pinfunction "1_1") (pintype "passive"))
      (node (ref "R11") (pin "2") (pinfunction "2_2") (pintype "passive"))
      (node (ref "R16") (pin "2") (pinfunction "2_2") (pintype "passive"))
      (node (ref "R18") (pin "2") (pinfunction "2_2") (pintype "passive"))
      (node (ref "R20") (pin "2") (pinfunction "2_2") (pintype "passive"))
      (node (ref "R25") (pin "2") (pinfunction "2_2") (pintype "passive"))
      (node (ref "R26") (pin "2") (pinfunction "2_2") (pintype "passive"))
      (node (ref "R27") (pin "2") (pinfunction "2_2") (pintype "passive"))
      (node (ref "R28") (pin "2") (pinfunction "2_2") (pintype "passive"))
      (node (ref "R29") (pin "2") (pinfunction "2_2") (pintype "passive"))
      (node (ref "R42") (pin "1") (pinfunction "1_1") (pintype "passive"))
      (node (ref "R46") (pin "2") (pinfunction "2_2") (pintype "passive"))
      (node (ref "R54") (pin "2") (pinfunction "2_2") (pintype "passive"))
      (node (ref "SJR1") (pin "8") (pinfunction "VCC_8") (pintype "bidirectional"))
      (node (ref "TP11") (pin "TP") (pinfunction "TP_TP") (pintype "input"))
      (node (ref "U$1") (pin "4") (pinfunction "FB_4") (pintype "bidirectional"))
      (node (ref "U1") (pin "8") (pinfunction "VCC_8") (pintype "bidirectional"))
      (node (ref "U2") (pin "2") (pinfunction "3V3_2") (pintype "bidirectional"))
      (node (ref "U4") (pin "8") (pinfunction "VCC_8") (pintype "bidirectional"))
      (node (ref "U6") (pin "1") (pinfunction "VDDIO_1") (pintype "bidirectional"))
      (node (ref "U6") (pin "14") (pinfunction "VDD_14") (pintype "bidirectional"))
    )
    (net (code "2") (name "5V") (class "Default")
      (node (ref "C14") (pin "+") (pinfunction "+_+") (pintype "passive"))
      (node (ref "C15") (pin "+") (pinfunction "+_+") (pintype "passive"))
      (node (ref "C22") (pin "1") (pinfunction "1_1") (pintype "passive"))
      (node (ref "C4") (pin "1") (pinfunction "1_1") (pintype "passive"))
      (node (ref "C5") (pin "1") (pinfunction "1_1") (pintype "passive"))
      (node (ref "C6") (pin "1") (pinfunction "1_1") (pintype "passive"))
      (node (ref "C9") (pin "1") (pinfunction "1_1") (pintype "passive"))
      (node (ref "D4") (pin "1") (pinfunction "A_1") (pintype "passive"))
      (node (ref "IC2") (pin "5") (pinfunction "V+_5") (pintype "power_in"))
      (node (ref "J3") (pin "VBUS") (pinfunction "VBUS_VBUS") (pintype "power_in"))
      (node (ref "LED_12") (pin "2") (pinfunction "2_2") (pintype "passive"))
      (node (ref "LED_24") (pin "2") (pinfunction "2_2") (pintype "passive"))
      (node (ref "R22") (pin "2") (pinfunction "2_2") (pintype "passive"))
      (node (ref "R32") (pin "1") (pinfunction "1_1") (pintype "passive"))
      (node (ref "R34") (pin "2") (pinfunction "2_2") (pintype "passive"))
      (node (ref "R41") (pin "2") (pinfunction "2_2") (pintype "passive"))
      (node (ref "R43") (pin "2") (pinfunction "2_2") (pintype "passive"))
      (node (ref "TP28") (pin "TP") (pinfunction "TP_TP") (pintype "input"))
      (node (ref "TP29") (pin "TP") (pinfunction "TP_TP") (pintype "input"))
      (node (ref "U$1") (pin "1") (pinfunction "VIN_1") (pintype "bidirectional"))
    )
    (net (code "3") (name "ACTIVE") (class "Default")
      (node (ref "IC1") (pin "11") (pinfunction "~{SUSPEND}_11") (pintype "output"))
      (node (ref "R40") (pin "2") (pinfunction "2_2") (pintype "passive"))
    )
    (net (code "4") (name "ADC") (class "Default")
      (node (ref "C31") (pin "2") (pinfunction "2_2") (pintype "passive"))
      (node (ref "R14") (pin "2") (pinfunction "2_2") (pintype "passive"))
      (node (ref "R15") (pin "2") (pinfunction "2_2") (pintype "passive"))
      (node (ref "SJR1") (pin "2") (pinfunction "ADC_2") (pintype "bidirectional"))
      (node (ref "U2") (pin "4") (pinfunction "SENSOR_VP/I36_4") (pintype "bidirectional"))
    )
    (net (code "5") (name "DTR") (class "Default")
      (node (ref "IC1") (pin "28") (pinfunction "DTR_28") (pintype "output"))
      (node (ref "R1") (pin "2") (pinfunction "2_2") (pintype "passive"))
      (node (ref "T1") (pin "2") (pinfunction "E_2") (pintype "passive"))
      (node (ref "U3") (pin "13") (pinfunction "~{DTR}_13") (pintype "bidirectional"))
    )
    (net (code "6") (name "D_N") (class "Default")
      (node (ref "J3") (pin "D-") (pinfunction "D-_D-") (pintype "bidirectional"))
      (node (ref "R6") (pin "1") (pinfunction "1_1") (pintype "passive"))
      (node (ref "R9") (pin "1") (pinfunction "1_1") (pintype "passive"))
    )
    (net (code "7") (name "D_N_CP") (class "Default")
      (node (ref "IC1") (pin "5") (pinfunction "D-_5") (pintype "bidirectional"))
      (node (ref "R6") (pin "2") (pinfunction "2_2") (pintype "passive"))
    )
    (net (code "8") (name "D_P") (class "Default")
      (node (ref "J3") (pin "D+") (pinfunction "D+_D+") (pintype "bidirectional"))
      (node (ref "R5") (pin "1") (pinfunction "1_1") (pintype "passive"))
      (node (ref "R8") (pin "1") (pinfunction "1_1") (pintype "passive"))
    )
    (net (code "9") (name "D_P_CP") (class "Default")
      (node (ref "IC1") (pin "4") (pinfunction "D+_4") (pintype "bidirectional"))
      (node (ref "R5") (pin "2") (pinfunction "2_2") (pintype "passive"))
    )
    (net (code "10") (name "EN") (class "Default")
      (node (ref "R26") (pin "1") (pinfunction "1_1") (pintype "passive"))
      (node (ref "SJR1") (pin "3") (pinfunction "CH_PD_3") (pintype "bidirectional"))
    )
    (net (code "11") (name "FLASH_CS") (class "Default")
      (node (ref "R17") (pin "2") (pinfunction "2_2") (pintype "passive"))
      (node (ref "R31") (pin "2") (pinfunction "2_2") (pintype "passive"))
      (node (ref "R49") (pin "1") (pinfunction "1_1") (pintype "passive"))
      (node (ref "R50") (pin "1") (pinfunction "1_1") (pintype "passive"))
      (node (ref "U4") (pin "1") (pinfunction "~{CS}_1") (pintype "bidirectional"))
    )
    (net (code "12") (name "GND") (class "Default")
      (node (ref "BT1") (pin "2") (pinfunction "-_2") (pintype "power_in"))
      (node (ref "C1") (pin "1") (pinfunction "1_1") (pintype "passive"))
      (node (ref "C10") (pin "2") (pinfunction "2_2") (pintype "passive"))
      (node (ref "C11") (pin "2") (pinfunction "2_2") (pintype "passive"))
      (node (ref "C12") (pin "2") (pinfunction "2_2") (pintype "passive"))
      (node (ref "C13") (pin "2") (pinfunction "2_2") (pintype "passive"))
      (node (ref "C14") (pin "-") (pinfunction "-_-") (pintype "passive"))
      (node (ref "C15") (pin "-") (pinfunction "-_-") (pintype "passive"))
      (node (ref "C16") (pin "2") (pinfunction "2_2") (pintype "passive"))
      (node (ref "C17") (pin "2") (pinfunction "2_2") (pintype "passive"))
      (node (ref "C18") (pin "1") (pinfunction "1_1") (pintype "passive"))
      (node (ref "C2") (pin "2") (pinfunction "2_2") (pintype "passive"))
      (node (ref "C21") (pin "2") (pinfunction "2_2") (pintype "passive"))
      (node (ref "C22") (pin "2") (pinfunction "2_2") (pintype "passive"))
      (node (ref "C23") (pin "-") (pinfunction "-_-") (pintype "passive"))
      (node (ref "C24") (pin "2") (pinfunction "2_2") (pintype "passive"))
      (node (ref "C25") (pin "2") (pinfunction "2_2") (pintype "passive"))
      (node (ref "C26") (pin "2") (pinfunction "2_2") (pintype "passive"))
      (node (ref "C27") (pin "2") (pinfunction "2_2") (pintype "passive"))
      (node (ref "C28") (pin "2") (pinfunction "2_2") (pintype "passive"))
      (node (ref "C29") (pin "2") (pinfunction "2_2") (pintype "passive"))
      (node (ref "C3") (pin "2") (pinfunction "2_2") (pintype "passive"))
      (node (ref "C30") (pin "2") (pinfunction "2_2") (pintype "passive"))
      (node (ref "C31") (pin "1") (pinfunction "1_1") (pintype "passive"))
      (node (ref "C4") (pin "2") (pinfunction "2_2") (pintype "passive"))
      (node (ref "C5") (pin "2") (pinfunction "2_2") (pintype "passive"))
      (node (ref "C6") (pin "2") (pinfunction "2_2") (pintype "passive"))
      (node (ref "C7") (pin "2") (pinfunction "2_2") (pintype "passive"))
      (node (ref "C8") (pin "2") (pinfunction "2_2") (pintype "passive"))
      (node (ref "C9") (pin "2") (pinfunction "2_2") (pintype "passive"))
      (node (ref "D1") (pin "3") (pinfunction "VSS_3") (pintype "bidirectional"))
      (node (ref "IC1") (pin "3") (pinfunction "GND_3") (pintype "power_in"))
      (node (ref "IC1") (pin "EXP") (pinfunction "GND_EXP") (pintype "power_in"))
      (node (ref "IC1") (pin "M") (pinfunction "GND_M") (pintype "power_in"))
      (node (ref "IC2") (pin "2") (pinfunction "V-_2") (pintype "power_in"))
      (node (ref "J1") (pin "6") (pinfunction "GND_6") (pintype "passive"))
      (node (ref "J3") (pin "GND") (pinfunction "GND_GND") (pintype "power_in"))
      (node (ref "LED_12") (pin "3") (pinfunction "3_3") (pintype "passive"))
      (node (ref "LED_24") (pin "3") (pinfunction "3_3") (pintype "passive"))
      (node (ref "R15") (pin "1") (pinfunction "1_1") (pintype "passive"))
      (node (ref "R19") (pin "1") (pinfunction "1_1") (pintype "passive"))
      (node (ref "R21") (pin "2") (pinfunction "2_2") (pintype "passive"))
      (node (ref "R30") (pin "2") (pinfunction "2_2") (pintype "passive"))
      (node (ref "R35") (pin "1") (pinfunction "1_1") (pintype "passive"))
      (node (ref "R38") (pin "2") (pinfunction "2_2") (pintype "passive"))
      (node (ref "R40") (pin "1") (pinfunction "1_1") (pintype "passive"))
      (node (ref "R44") (pin "1") (pinfunction "1_1") (pintype "passive"))
      (node (ref "R45") (pin "1") (pinfunction "1_1") (pintype "passive"))
      (node (ref "SJR1") (pin "9") (pinfunction "GND_9") (pintype "bidirectional"))
      (node (ref "T3") (pin "2") (pinfunction "E_2") (pintype "passive"))
      (node (ref "TP13") (pin "TP") (pinfunction "TP_TP") (pintype "input"))
      (node (ref "TP30") (pin "TP") (pinfunction "TP_TP") (pintype "input"))
      (node (ref "U$1") (pin "2") (pinfunction "GND_2") (pintype "bidirectional"))
      (node (ref "U1") (pin "4") (pinfunction "GND_4") (pintype "bidirectional"))
      (node (ref "U2") (pin "1") (pinfunction "GND_1") (pintype "bidirectional"))
      (node (ref "U2") (pin "15") (pinfunction "GND_15") (pintype "bidirectional"))
      (node (ref "U2") (pin "38") (pinfunction "GND_38") (pintype "bidirectional"))
      (node (ref "U2") (pin "GND") (pinfunction "GND_GND") (pintype "bidirectional"))
      (node (ref "U3") (pin "1") (pinfunction "GND_1") (pintype "bidirectional"))
      (node (ref "U4") (pin "4") (pinfunction "GND_4") (pintype "bidirectional"))
      (node (ref "U6") (pin "10") (pinfunction "GND_10") (pintype "bidirectional"))
      (node (ref "U6") (pin "12") (pinfunction "GND_12") (pintype "bidirectional"))
      (node (ref "U6") (pin "5") (pinfunction "GND_5") (pintype "bidirectional"))
    )
    (net (code "13") (name "GPIO0") (class "Default")
      (node (ref "R55") (pin "1") (pinfunction "1_1") (pintype "passive"))
      (node (ref "T1") (pin "3") (pinfunction "C_3") (pintype "passive"))
    )
    (net (code "14") (name "GPIO2") (class "Default")
      (node (ref "R28") (pin "1") (pinfunction "1_1") (pintype "passive"))
      (node (ref "SJR1") (pin "11") (pinfunction "GPIO2_11") (pintype "bidirectional"))
      (node (ref "U2") (pin "24") (pinfunction "IO2_24") (pintype "bidirectional"))
    )
    (net (code "15") (name "GPIO5") (class "Default")
      (node (ref "R13") (pin "1") (pinfunction "1_1") (pintype "passive"))
      (node (ref "SJR1") (pin "14") (pinfunction "GPIO5_14") (pintype "bidirectional"))
      (node (ref "TP2") (pin "TP") (pinfunction "TP_TP") (pintype "input"))
    )
    (net (code "16") (name "GPIO15") (class "Default")
      (node (ref "R30") (pin "1") (pinfunction "1_1") (pintype "passive"))
      (node (ref "SJR1") (pin "10") (pinfunction "GPIO15_10") (pintype "bidirectional"))
    )
    (net (code "17") (name "GPIO16") (class "Default")
      (node (ref "SJR1") (pin "4") (pinfunction "GPIO16_4") (pintype "bidirectional"))
      (node (ref "TP1") (pin "TP") (pinfunction "TP_TP") (pintype "input"))
    )
    (net (code "18") (name "INT1") (class "Default")
      (node (ref "SJR1") (pin "7") (pinfunction "GPIO13_7") (pintype "bidirectional"))
      (node (ref "TP4") (pin "TP") (pinfunction "TP_TP") (pintype "input"))
      (node (ref "U2") (pin "10") (pinfunction "IO25_10") (pintype "bidirectional"))
      (node (ref "U6") (pin "11") (pinfunction "INT1_11") (pintype "bidirectional"))
    )
    (net (code "19") (name "INT2") (class "Default")
      (node (ref "U2") (pin "11") (pinfunction "IO26_11") (pintype "bidirectional"))
      (node (ref "U6") (pin "9") (pinfunction "INT2_9") (pintype "bidirectional"))
    )
    (net (code "20") (name "LED_24_DI") (class "Default")
      (node (ref "LED_24") (pin "1") (pinfunction "1_1") (pintype "passive"))
      (node (ref "R23") (pin "1") (pinfunction "1_1") (pintype "passive"))
    )
    (net (code "21") (name "LED_WS") (class "Default")
      (node (ref "D1") (pin "4") (pinfunction "DI_4") (pintype "bidirectional"))
      (node (ref "R51") (pin "1") (pinfunction "1_1") (pintype "passive"))
      (node (ref "R52") (pin "1") (pinfunction "1_1") (pintype "passive"))
      (node (ref "SJR1") (pin "6") (pinfunction "GPIO12_6") (pintype "bidirectional"))
    )
    (net (code "22") (name "MISO") (class "Default")
      (node (ref "R54") (pin "1") (pinfunction "1_1") (pintype "passive"))
      (node (ref "SJR1") (pin "18") (pinfunction "MISO_18") (pintype "bidirectional"))
      (node (ref "U4") (pin "2") (pinfunction "SO(D1)_2") (pintype "bidirectional"))
    )
    (net (code "23") (name "MOSI") (class "Default")
      (node (ref "SJR1") (pin "21") (pinfunction "MOSI_21") (pintype "bidirectional"))
      (node (ref "TP5") (pin "TP") (pinfunction "TP_TP") (pintype "input"))
      (node (ref "U4") (pin "5") (pinfunction "SI(D0)_5") (pintype "bidirectional"))
    )
    (net (code "24") (name "NRST") (class "Default")
      (node (ref "C16") (pin "1") (pinfunction "1_1") (pintype "passive"))
      (node (ref "R25") (pin "1") (pinfunction "1_1") (pintype "passive"))
      (node (ref "SJR1") (pin "1") (pinfunction "REST_1") (pintype "bidirectional"))
      (node (ref "T2") (pin "3") (pinfunction "C_3") (pintype "passive"))
      (node (ref "U2") (pin "3") (pinfunction "EN_3") (pintype "bidirectional"))
    )
    (net (code "25") (name "Net-(C18-Pad2)") (class "Default")
      (node (ref "C18") (pin "2") (pinfunction "2_2") (pintype "passive"))
      (node (ref "C19") (pin "2") (pinfunction "2_2") (pintype "passive"))
      (node (ref "R33") (pin "2") (pinfunction "2_2") (pintype "passive"))
      (node (ref "R39") (pin "2") (pinfunction "2_2") (pintype "passive"))
    )
    (net (code "26") (name "Net-(C19-Pad1)") (class "Default")
      (node (ref "C19") (pin "1") (pinfunction "1_1") (pintype "passive"))
      (node (ref "R37") (pin "2") (pinfunction "2_2") (pintype "passive"))
    )
    (net (code "27") (name "Net-(D1-DO)") (class "Default")
      (node (ref "D1") (pin "2") (pinfunction "DO_2") (pintype "bidirectional"))
      (node (ref "R23") (pin "2") (pinfunction "2_2") (pintype "passive"))
    )
    (net (code "28") (name "Net-(D1-VDD)") (class "Default")
      (node (ref "C1") (pin "2") (pinfunction "2_2") (pintype "passive"))
      (node (ref "D1") (pin "1") (pinfunction "VDD_1") (pintype "bidirectional"))
      (node (ref "D3") (pin "3") (pinfunction "K_3") (pintype "passive"))
    )
    (net (code "29") (name "Net-(D3-A)") (class "Default")
      (node (ref "D3") (pin "1") (pinfunction "A_1") (pintype "passive"))
      (node (ref "R22") (pin "1") (pinfunction "1_1") (pintype "passive"))
    )
    (net (code "30") (name "Net-(D4-K)") (class "Default")
      (node (ref "D4") (pin "3") (pinfunction "K_3") (pintype "passive"))
      (node (ref "U3") (pin "16") (pinfunction "VCC_16") (pintype "bidirectional"))
    )
    (net (code "31") (name "Net-(IC1-RXD)") (class "Default")
      (node (ref "IC1") (pin "25") (pinfunction "RXD_25") (pintype "input"))
      (node (ref "R4") (pin "2") (pinfunction "2_2") (pintype "passive"))
    )
    (net (code "32") (name "Net-(IC1-TXD)") (class "Default")
      (node (ref "IC1") (pin "26") (pinfunction "TXD_26") (pintype "output"))
      (node (ref "R3") (pin "2") (pinfunction "2_2") (pintype "passive"))
    )
    (net (code "33") (name "Net-(IC1-VBUS)") (class "Default")
      (node (ref "IC1") (pin "8") (pinfunction "VBUS_8") (pintype "input"))
      (node (ref "R43") (pin "1") (pinfunction "1_1") (pintype "passive"))
      (node (ref "R44") (pin "2") (pinfunction "2_2") (pintype "passive"))
    )
    (net (code "34") (name "Net-(IC1-~{RST})") (class "Default")
      (node (ref "IC1") (pin "9") (pinfunction "~{RST}_9") (pintype "bidirectional"))
      (node (ref "R42") (pin "2") (pinfunction "2_2") (pintype "passive"))
    )
    (net (code "35") (name "Net-(IC2-+IN)") (class "Default")
      (node (ref "IC2") (pin "1") (pinfunction "+IN_1") (pintype "input"))
      (node (ref "R34") (pin "1") (pinfunction "1_1") (pintype "passive"))
      (node (ref "R35") (pin "2") (pinfunction "2_2") (pintype "passive"))
    )
    (net (code "36") (name "Net-(IC2--IN)") (class "Default")
      (node (ref "IC2") (pin "3") (pinfunction "-IN_3") (pintype "input"))
      (node (ref "R36") (pin "2") (pinfunction "2_2") (pintype "passive"))
      (node (ref "R37") (pin "1") (pinfunction "1_1") (pintype "passive"))
    )
    (net (code "37") (name "Net-(IC2-OUT)") (class "Default")
      (node (ref "C20") (pin "2") (pinfunction "2_2") (pintype "passive"))
      (node (ref "IC2") (pin "4") (pinfunction "OUT_4") (pintype "output"))
      (node (ref "R36") (pin "1") (pinfunction "1_1") (pintype "passive"))
    )
    (net (code "38") (name "Net-(J1-VCC)") (class "Default")
      (node (ref "J1") (pin "4") (pinfunction "VCC_4") (pintype "passive"))
      (node (ref "R11") (pin "1") (pinfunction "1_1") (pintype "passive"))
    )
    (net (code "39") (name "Net-(J3-PadSHIELD)") (class "Default")
      (node (ref "J3") (pin "SHIELD") (pinfunction "SHIELD_SHIELD") (pintype "bidirectional"))
      (node (ref "J3") (pin "SHIELD10") (pinfunction "SHIELD_SHIELD10") (pintype "bidirectional"))
      (node (ref "J3") (pin "SHIELD2") (pinfunction "SHIELD_SHIELD2") (pintype "bidirectional"))
      (node (ref "J3") (pin "SHIELD3") (pinfunction "SHIELD_SHIELD3") (pintype "bidirectional"))
      (node (ref "J3") (pin "SHIELD4") (pinfunction "SHIELD_SHIELD4") (pintype "bidirectional"))
      (node (ref "J3") (pin "SHIELD5") (pinfunction "SHIELD_SHIELD5") (pintype "bidirectional"))
      (node (ref "J3") (pin "SHIELD6") (pinfunction "SHIELD_SHIELD6") (pintype "bidirectional"))
      (node (ref "J3") (pin "SHIELD7") (pinfunction "SHIELD_SHIELD7") (pintype "bidirectional"))
      (node (ref "J3") (pin "SHIELD8") (pinfunction "SHIELD_SHIELD8") (pintype "bidirectional"))
      (node (ref "J3") (pin "SHIELD9") (pinfunction "SHIELD_SHIELD9") (pintype "bidirectional"))
      (node (ref "R21") (pin "1") (pinfunction "1_1") (pintype "passive"))
    )
    (net (code "40") (name "Net-(LED_12-Pad1)") (class "Default")
      (node (ref "LED_12") (pin "1") (pinfunction "1_1") (pintype "passive"))
      (node (ref "R24") (pin "1") (pinfunction "1_1") (pintype "passive"))
    )
    (net (code "41") (name "Net-(LED_24-Pad4)") (class "Default")
      (node (ref "LED_24") (pin "4") (pinfunction "4_4") (pintype "passive"))
      (node (ref "R24") (pin "2") (pinfunction "2_2") (pintype "passive"))
    )
    (net (code "42") (name "Net-(LIGHT_DR-Pad2)") (class "Default")
      (node (ref "LIGHT_DR") (pin "2") (pinfunction "2_2") (pintype "passive"))
      (node (ref "R14") (pin "1") (pinfunction "1_1") (pintype "passive"))
      (node (ref "R18") (pin "1") (pinfunction "1_1") (pintype "passive"))
      (node (ref "R19") (pin "2") (pinfunction "2_2") (pintype "passive"))
      (node (ref "R20") (pin "1") (pinfunction "1_1") (pintype "passive"))
    )
    (net (code "43") (name "Net-(LS1-1)") (class "Default")
      (node (ref "C20") (pin "1") (pinfunction "1_1") (pintype "passive"))
      (node (ref "LS1") (pin "+") (pinfunction "1_+") (pintype "passive"))
      (node (ref "R32") (pin "2") (pinfunction "2_2") (pintype "passive"))
      (node (ref "R47") (pin "2") (pinfunction "2_2") (pintype "passive"))
    )
    (net (code "44") (name "Net-(LS1-2)") (class "Default")
      (node (ref "LS1") (pin "-") (pinfunction "2_-") (pintype "passive"))
      (node (ref "R38") (pin "1") (pinfunction "1_1") (pintype "passive"))
      (node (ref "R47") (pin "1") (pinfunction "1_1") (pintype "passive"))
      (node (ref "T3") (pin "3") (pinfunction "C_3") (pintype "passive"))
    )
    (net (code "45") (name "Net-(SJR1-CS0)") (class "Default")
      (node (ref "R17") (pin "1") (pinfunction "1_1") (pintype "passive"))
      (node (ref "SJR1") (pin "17") (pinfunction "CS0_17") (pintype "bidirectional"))
    )
    (net (code "46") (name "Net-(SJR1-GPIO14)") (class "Default")
      (node (ref "R31") (pin "1") (pinfunction "1_1") (pintype "passive"))
      (node (ref "SJR1") (pin "5") (pinfunction "GPIO14_5") (pintype "bidirectional"))
      (node (ref "TP3") (pin "TP") (pinfunction "TP_TP") (pintype "input"))
    )
    (net (code "47") (name "Net-(T1-B)") (class "Default")
      (node (ref "R2") (pin "1") (pinfunction "1_1") (pintype "passive"))
      (node (ref "T1") (pin "1") (pinfunction "B_1") (pintype "passive"))
    )
    (net (code "48") (name "Net-(T2-B)") (class "Default")
      (node (ref "R1") (pin "1") (pinfunction "1_1") (pintype "passive"))
      (node (ref "T2") (pin "1") (pinfunction "B_1") (pintype "passive"))
    )
    (net (code "49") (name "Net-(T3-B)") (class "Default")
      (node (ref "R39") (pin "1") (pinfunction "1_1") (pintype "passive"))
      (node (ref "T3") (pin "1") (pinfunction "B_1") (pintype "passive"))
    )
    (net (code "50") (name "Net-(U$1-EN)") (class "Default")
      (node (ref "R41") (pin "1") (pinfunction "1_1") (pintype "passive"))
      (node (ref "U$1") (pin "3") (pinfunction "EN_3") (pintype "bidirectional"))
    )
    (net (code "51") (name "Net-(U$1-SW)") (class "Default")
      (node (ref "L1") (pin "1") (pinfunction "1_1") (pintype "passive"))
      (node (ref "U$1") (pin "5") (pinfunction "SW_5") (pintype "bidirectional"))
    )
    (net (code "52") (name "Net-(U1-X1)") (class "Default")
      (node (ref "U1") (pin "1") (pinfunction "X1_1") (pintype "bidirectional"))
      (node (ref "Y2") (pin "P$2") (pinfunction "2_P$2") (pintype "passive"))
    )
    (net (code "53") (name "Net-(U1-X2)") (class "Default")
      (node (ref "U1") (pin "2") (pinfunction "X2_2") (pintype "bidirectional"))
      (node (ref "Y2") (pin "P$1") (pinfunction "1_P$1") (pintype "passive"))
    )
    (net (code "54") (name "Net-(U2-CS0_H{slash}IO15)") (class "Default")
      (node (ref "R48") (pin "2") (pinfunction "2_2") (pintype "passive"))
      (node (ref "R49") (pin "2") (pinfunction "2_2") (pintype "passive"))
      (node (ref "U2") (pin "23") (pinfunction "CS0_H/IO15_23") (pintype "bidirectional"))
    )
    (net (code "55") (name "Net-(U2-CS0_V{slash}IO5)") (class "Default")
      (node (ref "R50") (pin "2") (pinfunction "2_2") (pintype "passive"))
      (node (ref "U2") (pin "29") (pinfunction "CS0_V/IO5_29") (pintype "bidirectional"))
    )
    (net (code "56") (name "Net-(U2-IO0)") (class "Default")
      (node (ref "TP27") (pin "TP") (pinfunction "TP_TP") (pintype "input"))
      (node (ref "U2") (pin "25") (pinfunction "IO0_25") (pintype "bidirectional"))
    )
    (net (code "57") (name "Net-(U2-IO4)") (class "Default")
      (node (ref "TP17") (pin "TP") (pinfunction "TP_TP") (pintype "input"))
      (node (ref "U2") (pin "26") (pinfunction "IO4_26") (pintype "bidirectional"))
    )
    (net (code "58") (name "Net-(U2-IO16)") (class "Default")
      (node (ref "TP25") (pin "TP") (pinfunction "TP_TP") (pintype "input"))
      (node (ref "U2") (pin "27") (pinfunction "IO16_27") (pintype "bidirectional"))
    )
    (net (code "59") (name "Net-(U2-IO17)") (class "Default")
      (node (ref "TP26") (pin "TP") (pinfunction "TP_TP") (pintype "input"))
      (node (ref "U2") (pin "28") (pinfunction "IO17_28") (pintype "bidirectional"))
    )
    (net (code "60") (name "Net-(U2-IO21)") (class "Default")
      (node (ref "R51") (pin "2") (pinfunction "2_2") (pintype "passive"))
      (node (ref "U2") (pin "33") (pinfunction "IO21_33") (pintype "bidirectional"))
    )
    (net (code "61") (name "Net-(U2-IO22)") (class "Default")
      (node (ref "R52") (pin "2") (pinfunction "2_2") (pintype "passive"))
      (node (ref "U2") (pin "36") (pinfunction "IO22_36") (pintype "bidirectional"))
    )
    (net (code "62") (name "Net-(U2-IO34)") (class "Default")
      (node (ref "TP15") (pin "TP") (pinfunction "TP_TP") (pintype "input"))
      (node (ref "U2") (pin "6") (pinfunction "IO34_6") (pintype "bidirectional"))
    )
    (net (code "63") (name "Net-(U2-IO35)") (class "Default")
      (node (ref "TP14") (pin "TP") (pinfunction "TP_TP") (pintype "input"))
      (node (ref "U2") (pin "7") (pinfunction "IO35_7") (pintype "bidirectional"))
    )
    (net (code "64") (name "Net-(U2-MISO_H{slash}IO12)") (class "Default")
      (node (ref "TP10") (pin "TP") (pinfunction "TP_TP") (pintype "input"))
      (node (ref "U2") (pin "14") (pinfunction "MISO_H/IO12_14") (pintype "bidirectional"))
    )
    (net (code "65") (name "Net-(U2-MOSI_H{slash}IO13)") (class "Default")
      (node (ref "TP12") (pin "TP") (pinfunction "TP_TP") (pintype "input"))
      (node (ref "U2") (pin "16") (pinfunction "MOSI_H/IO13_16") (pintype "bidirectional"))
    )
    (net (code "66") (name "Net-(U2-MOSI_V{slash}IO23)") (class "Default")
      (node (ref "R53") (pin "2") (pinfunction "2_2") (pintype "passive"))
      (node (ref "U2") (pin "37") (pinfunction "MOSI_V/IO23_37") (pintype "bidirectional"))
    )
    (net (code "67") (name "Net-(U2-SCK_H{slash}IO14)") (class "Default")
      (node (ref "TP24") (pin "TP") (pinfunction "TP_TP") (pintype "input"))
      (node (ref "U2") (pin "13") (pinfunction "SCK_H/IO14_13") (pintype "bidirectional"))
    )
    (net (code "68") (name "Net-(U2-SCK{slash}IO6)") (class "Default")
      (node (ref "TP21") (pin "TP") (pinfunction "TP_TP") (pintype "input"))
      (node (ref "U2") (pin "20") (pinfunction "SCK/IO6_20") (pintype "bidirectional"))
    )
    (net (code "69") (name "Net-(U2-SCS{slash}IO11)") (class "Default")
      (node (ref "TP20") (pin "TP") (pinfunction "TP_TP") (pintype "input"))
      (node (ref "U2") (pin "19") (pinfunction "SCS/IO11_19") (pintype "bidirectional"))
    )
    (net (code "70") (name "Net-(U2-SDI{slash}IO8)") (class "Default")
      (node (ref "TP23") (pin "TP") (pinfunction "TP_TP") (pintype "input"))
      (node (ref "U2") (pin "22") (pinfunction "SDI/IO8_22") (pintype "bidirectional"))
    )
    (net (code "71") (name "Net-(U2-SDO{slash}IO7)") (class "Default")
      (node (ref "TP22") (pin "TP") (pinfunction "TP_TP") (pintype "input"))
      (node (ref "U2") (pin "21") (pinfunction "SDO/IO7_21") (pintype "bidirectional"))
    )
    (net (code "72") (name "Net-(U2-SENSOR_VN{slash}I39)") (class "Default")
      (node (ref "TP16") (pin "TP") (pinfunction "TP_TP") (pintype "input"))
      (node (ref "U2") (pin "5") (pinfunction "SENSOR_VN/I39_5") (pintype "bidirectional"))
    )
    (net (code "73") (name "Net-(U2-SHD{slash}IO9)") (class "Default")
      (node (ref "TP18") (pin "TP") (pinfunction "TP_TP") (pintype "input"))
      (node (ref "U2") (pin "17") (pinfunction "SHD/IO9_17") (pintype "bidirectional"))
    )
    (net (code "74") (name "Net-(U2-SWP{slash}IO10)") (class "Default")
      (node (ref "TP19") (pin "TP") (pinfunction "TP_TP") (pintype "input"))
      (node (ref "U2") (pin "18") (pinfunction "SWP/IO10_18") (pintype "bidirectional"))
    )
    (net (code "75") (name "Net-(U2-XTAL_N{slash}IO33)") (class "Default")
      (node (ref "C29") (pin "1") (pinfunction "1_1") (pintype "passive"))
      (node (ref "U2") (pin "9") (pinfunction "XTAL_N/IO33_9") (pintype "bidirectional"))
      (node (ref "Y3") (pin "P$1") (pinfunction "1_P$1") (pintype "passive"))
    )
    (net (code "76") (name "Net-(U2-XTAL_P{slash}IO32)") (class "Default")
      (node (ref "C30") (pin "1") (pinfunction "1_1") (pintype "passive"))
      (node (ref "U2") (pin "8") (pinfunction "XTAL_P/IO32_8") (pintype "bidirectional"))
      (node (ref "Y3") (pin "P$2") (pinfunction "2_P$2") (pintype "passive"))
    )
    (net (code "77") (name "Net-(U3-RXI)") (class "Default")
      (node (ref "R10") (pin "1") (pinfunction "1_1") (pintype "passive"))
      (node (ref "U3") (pin "3") (pinfunction "RXI_3") (pintype "bidirectional"))
    )
    (net (code "78") (name "Net-(U3-TXO)") (class "Default")
      (node (ref "R7") (pin "1") (pinfunction "1_1") (pintype "passive"))
      (node (ref "U3") (pin "2") (pinfunction "TXO_2") (pintype "bidirectional"))
    )
    (net (code "79") (name "Net-(U3-UD+)") (class "Default")
      (node (ref "R8") (pin "2") (pinfunction "2_2") (pintype "passive"))
      (node (ref "U3") (pin "5") (pinfunction "UD+_5") (pintype "bidirectional"))
    )
    (net (code "80") (name "Net-(U3-UD-)") (class "Default")
      (node (ref "R9") (pin "2") (pinfunction "2_2") (pintype "passive"))
      (node (ref "U3") (pin "6") (pinfunction "UD-_6") (pintype "bidirectional"))
    )
    (net (code "81") (name "Net-(U3-V3)") (class "Default")
      (node (ref "C13") (pin "1") (pinfunction "1_1") (pintype "passive"))
      (node (ref "U3") (pin "4") (pinfunction "V3_4") (pintype "bidirectional"))
    )
    (net (code "82") (name "Net-(U3-XI)") (class "Default")
      (node (ref "C7") (pin "1") (pinfunction "1_1") (pintype "passive"))
      (node (ref "U3") (pin "7") (pinfunction "XI_7") (pintype "bidirectional"))
      (node (ref "Y1") (pin "1") (pinfunction "1_1") (pintype "passive"))
      (node (ref "Y4") (pin "P$1") (pinfunction "1_P$1") (pintype "passive"))
    )
    (net (code "83") (name "Net-(U3-XO)") (class "Default")
      (node (ref "C8") (pin "1") (pinfunction "1_1") (pintype "passive"))
      (node (ref "U3") (pin "8") (pinfunction "XO_8") (pintype "bidirectional"))
      (node (ref "Y1") (pin "2") (pinfunction "2_2") (pintype "passive"))
      (node (ref "Y4") (pin "P$2") (pinfunction "2_P$2") (pintype "passive"))
    )
    (net (code "84") (name "Net-(U6-BYP)") (class "Default")
      (node (ref "C26") (pin "1") (pinfunction "1_1") (pintype "passive"))
      (node (ref "U6") (pin "2") (pinfunction "BYP_2") (pintype "bidirectional"))
    )
    (net (code "85") (name "Net-(U6-SA0)") (class "Default")
      (node (ref "R45") (pin "2") (pinfunction "2_2") (pintype "passive"))
      (node (ref "R46") (pin "1") (pinfunction "1_1") (pintype "passive"))
      (node (ref "U6") (pin "7") (pinfunction "SA0_7") (pintype "bidirectional"))
    )
    (net (code "86") (name "PWM") (class "Default")
      (node (ref "R12") (pin "2") (pinfunction "2_2") (pintype "passive"))
      (node (ref "R13") (pin "2") (pinfunction "2_2") (pintype "passive"))
      (node (ref "R33") (pin "1") (pinfunction "1_1") (pintype "passive"))
      (node (ref "R48") (pin "1") (pinfunction "1_1") (pintype "passive"))
      (node (ref "R53") (pin "1") (pinfunction "1_1") (pintype "passive"))
    )
    (net (code "87") (name "RTS") (class "Default")
      (node (ref "IC1") (pin "24") (pinfunction "RTS_24") (pintype "output"))
      (node (ref "R2") (pin "2") (pinfunction "2_2") (pintype "passive"))
      (node (ref "T2") (pin "2") (pinfunction "E_2") (pintype "passive"))
      (node (ref "U3") (pin "14") (pinfunction "~{RTS}_14") (pintype "bidirectional"))
    )
    (net (code "88") (name "RXD0") (class "Default")
      (node (ref "J1") (pin "3") (pinfunction "TXO_3") (pintype "passive"))
      (node (ref "R12") (pin "1") (pinfunction "1_1") (pintype "passive"))
      (node (ref "R3") (pin "1") (pinfunction "1_1") (pintype "passive"))
      (node (ref "R7") (pin "2") (pinfunction "2_2") (pintype "passive"))
      (node (ref "SJR1") (pin "15") (pinfunction "RXD_15") (pintype "bidirectional"))
      (node (ref "U2") (pin "34") (pinfunction "RXD_34") (pintype "bidirectional"))
    )
    (net (code "89") (name "SCL") (class "Default")
      (node (ref "R27") (pin "1") (pinfunction "1_1") (pintype "passive"))
      (node (ref "R55") (pin "2") (pinfunction "2_2") (pintype "passive"))
      (node (ref "SJR1") (pin "12") (pinfunction "GPIO0_12") (pintype "bidirectional"))
      (node (ref "TP6") (pin "TP") (pinfunction "TP_TP") (pintype "input"))
      (node (ref "U1") (pin "6") (pinfunction "SCL_6") (pintype "bidirectional"))
      (node (ref "U2") (pin "31") (pinfunction "MISO_V/IO19_31") (pintype "bidirectional"))
      (node (ref "U6") (pin "4") (pinfunction "SCL_4") (pintype "bidirectional"))
    )
    (net (code "90") (name "SCLK") (class "Default")
      (node (ref "SJR1") (pin "22") (pinfunction "SCLK_22") (pintype "bidirectional"))
      (node (ref "U4") (pin "6") (pinfunction "SCK_6") (pintype "bidirectional"))
    )
    (net (code "91") (name "SDA") (class "Default")
      (node (ref "R29") (pin "1") (pinfunction "1_1") (pintype "passive"))
      (node (ref "SJR1") (pin "13") (pinfunction "GPIO4_13") (pintype "bidirectional"))
      (node (ref "TP9") (pin "TP") (pinfunction "TP_TP") (pintype "input"))
      (node (ref "U1") (pin "5") (pinfunction "SDA_5") (pintype "bidirectional"))
      (node (ref "U2") (pin "30") (pinfunction "SCK_V/IO18_30") (pintype "bidirectional"))
      (node (ref "U6") (pin "6") (pinfunction "SDA_6") (pintype "bidirectional"))
    )
    (net (code "92") (name "SPI_HOLD") (class "Default")
      (node (ref "SJR1") (pin "19") (pinfunction "GPIO9_19") (pintype "bidirectional"))
      (node (ref "TP7") (pin "TP") (pinfunction "TP_TP") (pintype "input"))
      (node (ref "U4") (pin "7") (pinfunction "~{HOLD}(D3)_7") (pintype "bidirectional"))
    )
    (net (code "93") (name "SPI_WP") (class "Default")
      (node (ref "SJR1") (pin "20") (pinfunction "GPIO10_20") (pintype "bidirectional"))
      (node (ref "TP8") (pin "TP") (pinfunction "TP_TP") (pintype "input"))
      (node (ref "U4") (pin "3") (pinfunction "~{WP}(D2)_3") (pintype "bidirectional"))
    )
    (net (code "94") (name "SQW") (class "Default")
      (node (ref "R16") (pin "1") (pinfunction "1_1") (pintype "passive"))
      (node (ref "U1") (pin "7") (pinfunction "SQW_7") (pintype "bidirectional"))
    )
    (net (code "95") (name "TXD0") (class "Default")
      (node (ref "J1") (pin "2") (pinfunction "RXI_2") (pintype "passive"))
      (node (ref "R10") (pin "2") (pinfunction "2_2") (pintype "passive"))
      (node (ref "R4") (pin "1") (pinfunction "1_1") (pintype "passive"))
      (node (ref "SJR1") (pin "16") (pinfunction "TXD_16") (pintype "bidirectional"))
      (node (ref "U2") (pin "35") (pinfunction "TXD_35") (pintype "bidirectional"))
    )
    (net (code "96") (name "VBAT") (class "Default")
      (node (ref "BT1") (pin "1") (pinfunction "+_1") (pintype "power_in"))
      (node (ref "U1") (pin "3") (pinfunction "VBATT_3") (pintype "bidirectional"))
    )
    (net (code "97") (name "unconnected-(IC1-CTS-Pad23)") (class "Default")
      (node (ref "IC1") (pin "23") (pinfunction "CTS_23") (pintype "input"))
    )
    (net (code "98") (name "unconnected-(IC1-DCD-Pad1)") (class "Default")
      (node (ref "IC1") (pin "1") (pinfunction "DCD_1") (pintype "input"))
    )
    (net (code "99") (name "unconnected-(IC1-DSR-Pad27)") (class "Default")
      (node (ref "IC1") (pin "27") (pinfunction "DSR_27") (pintype "input"))
    )
    (net (code "100") (name "unconnected-(IC1-RI-Pad2)") (class "Default")
      (node (ref "IC1") (pin "2") (pinfunction "RI_2") (pintype "input"))
    )
    (net (code "101") (name "unconnected-(IC1-SUSPEND-Pad12)") (class "Default")
      (node (ref "IC1") (pin "12") (pinfunction "SUSPEND_12") (pintype "output"))
    )
    (net (code "102") (name "unconnected-(J1-CTS-Pad5)") (class "Default")
      (node (ref "J1") (pin "5") (pinfunction "CTS_5") (pintype "passive"))
    )
    (net (code "103") (name "unconnected-(J1-DTR-Pad1)") (class "Default")
      (node (ref "J1") (pin "1") (pinfunction "DTR_1") (pintype "passive"))
    )
    (net (code "104") (name "unconnected-(J3-PadID)") (class "Default")
      (node (ref "J3") (pin "ID") (pinfunction "ID_ID") (pintype "bidirectional"))
    )
    (net (code "105") (name "unconnected-(LED_12-Pad4)") (class "Default")
      (node (ref "LED_12") (pin "4") (pinfunction "4_4") (pintype "passive"))
    )
    (net (code "106") (name "unconnected-(U2-IO27-Pad12)") (class "Default")
      (node (ref "U2") (pin "12") (pinfunction "IO27_12") (pintype "bidirectional"))
    )
    (net (code "107") (name "unconnected-(U2-NC-Pad32)") (class "Default")
      (node (ref "U2") (pin "32") (pinfunction "NC_32") (pintype "bidirectional"))
    )
    (net (code "108") (name "unconnected-(U3-R232-Pad15)") (class "Default")
      (node (ref "U3") (pin "15") (pinfunction "R232_15") (pintype "bidirectional"))
    )
    (net (code "109") (name "unconnected-(U3-~{CTS}-Pad9)") (class "Default")
      (node (ref "U3") (pin "9") (pinfunction "~{CTS}_9") (pintype "bidirectional"))
    )
    (net (code "110") (name "unconnected-(U3-~{DCD}-Pad12)") (class "Default")
      (node (ref "U3") (pin "12") (pinfunction "~{DCD}_12") (pintype "bidirectional"))
    )
    (net (code "111") (name "unconnected-(U3-~{DSR}-Pad10)") (class "Default")
      (node (ref "U3") (pin "10") (pinfunction "~{DSR}_10") (pintype "bidirectional"))
    )
    (net (code "112") (name "unconnected-(U3-~{RI}-Pad11)") (class "Default")
      (node (ref "U3") (pin "11") (pinfunction "~{RI}_11") (pintype "bidirectional"))
    )
  )
)
